# USB_HUB.net
KiCad netlist of a schematic drawn in Altium Designer
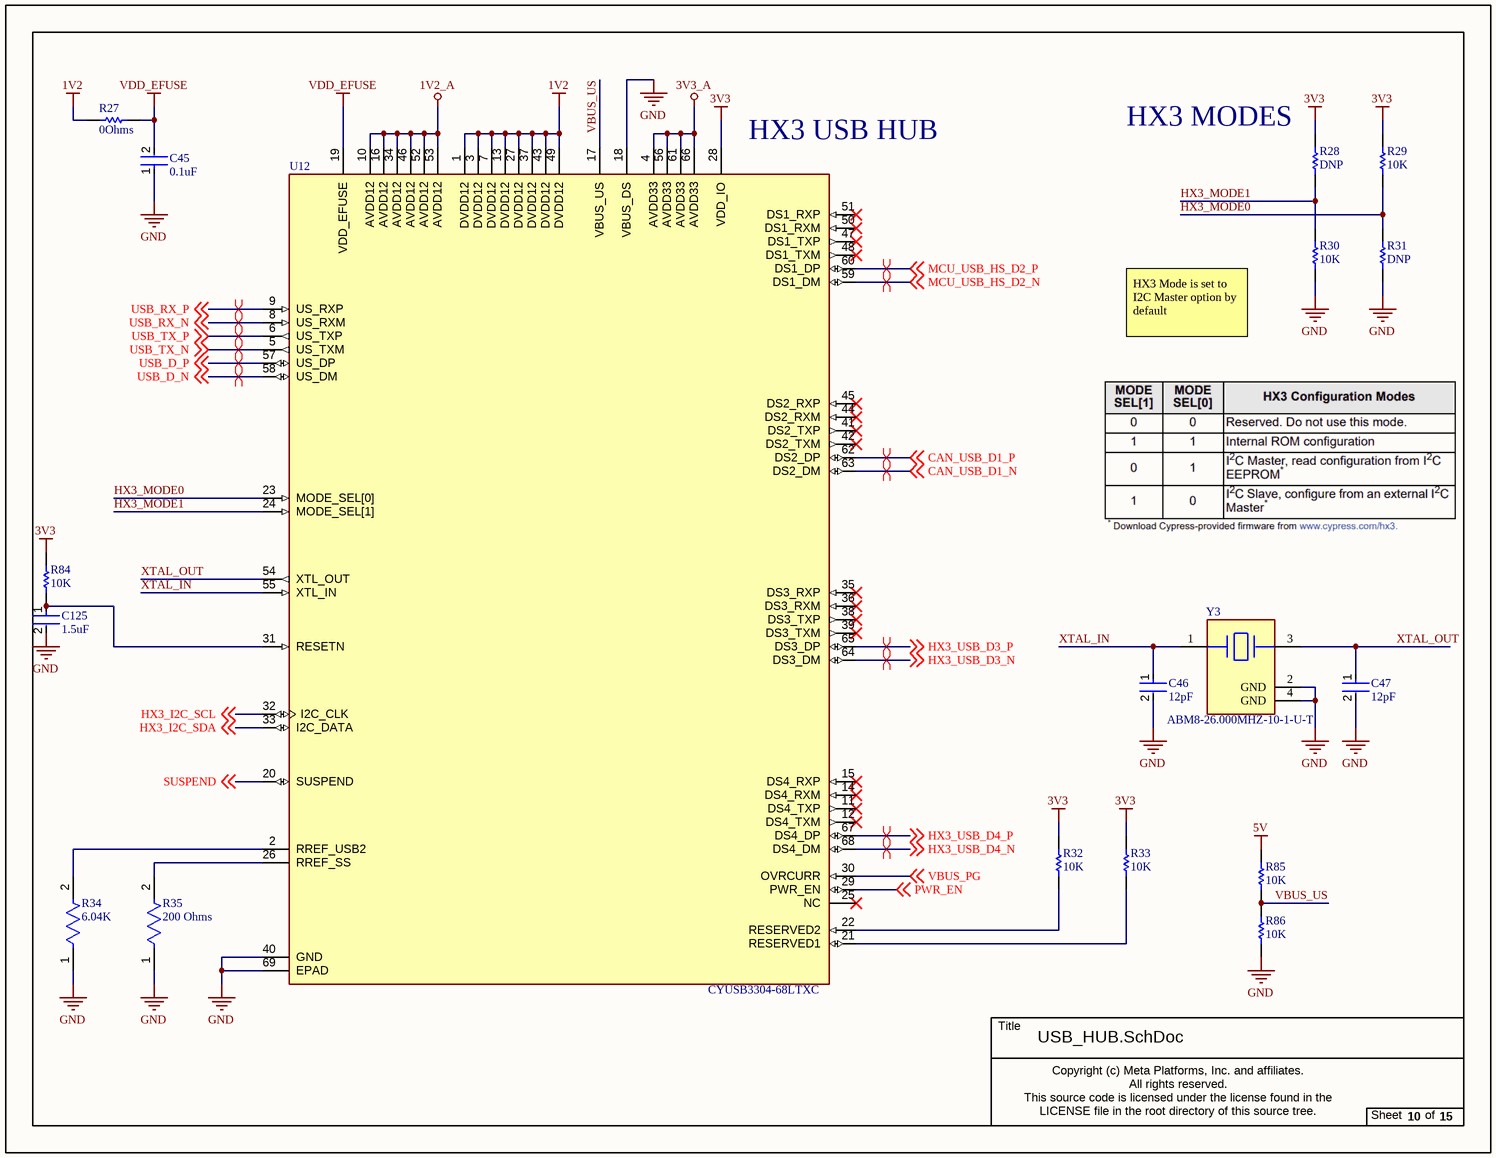
[diagram p0: USB_HUB.SchDoc]

(export (version "E")
  (design (tool "Eeschema 10.0.6"))
  (components
    (comp (ref "C45")
      (value "0.1uF")
      (footprint "FP-CC0201-BA-MFG")
      (description "CAP CER 0.1UF 6.3V X5R 0201")
      (fields (field (name "MANUFACTURER") "Yageo") (field (name "TOLERANCE") "0.1"))
      (libsource (lib "Altium Content Vault") (part "11868f565c42a9108669ba33697ecf6"))
    )
    (comp (ref "C46")
      (value "12pF")
      (footprint "FP-0402-L_1_0_1-W_0_5_0_1-IPC_B")
      (description "General Purpose Ceramic Capacitor, 0402, 12pF, 5%, C0G, 30ppm/°C, 50V")
      (fields (field (name "VOLTAGE") "50V") (field (name "TOLERANCE") "5%"))
      (libsource (lib "Altium Content Vault") (part "b4654b650e69147ec39a6b967a45e02"))
    )
    (comp (ref "C47")
      (value "12pF")
      (footprint "FP-0402-L_1_0_1-W_0_5_0_1-IPC_B")
      (description "General Purpose Ceramic Capacitor, 0402, 12pF, 5%, C0G, 30ppm/°C, 50V")
      (fields (field (name "VOLTAGE") "50V") (field (name "TOLERANCE") "5%"))
      (libsource (lib "Altium Content Vault") (part "b4654b650e69147ec39a6b967a45e02"))
    )
    (comp (ref "C125")
      (value "1.5uF")
      (footprint "FP-C1005-050-0_05-IPC_A")
      (description "Multilayer Ceramic Capacitors 1.5μF ±10% 10V X5R SMD 0402")
      (fields (field (name "TOLERANCE") "10%"))
      (libsource (lib "Altium Content Vault") (part "b4654b650e69147ec39a6b967a45e02"))
    )
    (comp (ref "R27")
      (value "0Ohms")
      (footprint "RESC1005X40X25ML05T10")
      (fields (field (name "PART NUMBER") "CRCW040210K0FKEDHP") (field (name "MANUFACTURER") "Vishay Dale"))
      (libsource (lib "Altium Content Vault") (part "RES"))
    )
    (comp (ref "R28")
      (value "DNP")
      (footprint "RESC1005X40X25ML05T10")
      (fields (field (name "PART NUMBER") "CRCW040210K0FKEDHP") (field (name "MANUFACTURER") "Vishay Dale"))
      (libsource (lib "Altium Content Vault") (part "RES"))
    )
    (comp (ref "R29")
      (value "10K")
      (footprint "RESC1005X40X25ML05T10")
      (fields (field (name "PART NUMBER") "CRCW040210K0FKEDHP") (field (name "MANUFACTURER") "Vishay Dale"))
      (libsource (lib "Altium Content Vault") (part "RES"))
    )
    (comp (ref "R30")
      (value "10K")
      (footprint "RESC1005X40X25ML05T10")
      (fields (field (name "PART NUMBER") "CRCW040210K0FKEDHP") (field (name "MANUFACTURER") "Vishay Dale"))
      (libsource (lib "Altium Content Vault") (part "RES"))
    )
    (comp (ref "R31")
      (value "DNP")
      (footprint "RESC1005X40X25ML05T10")
      (fields (field (name "PART NUMBER") "CRCW040210K0FKEDHP") (field (name "MANUFACTURER") "Vishay Dale"))
      (libsource (lib "Altium Content Vault") (part "RES"))
    )
    (comp (ref "R32")
      (value "10K")
      (footprint "RESC1005X40X25ML05T10")
      (fields (field (name "PART NUMBER") "CRCW040210K0FKEDHP") (field (name "MANUFACTURER") "Vishay Dale"))
      (libsource (lib "Altium Content Vault") (part "RES"))
    )
    (comp (ref "R33")
      (value "10K")
      (footprint "RESC1005X40X25ML05T10")
      (fields (field (name "PART NUMBER") "CRCW040210K0FKEDHP") (field (name "MANUFACTURER") "Vishay Dale"))
      (libsource (lib "Altium Content Vault") (part "RES"))
    )
    (comp (ref "R34")
      (value "6.04K")
      (footprint "FP-RMCF0402-IPC_A")
      (description "6.04kΩ ±1% 0.063W 0402 Thick Film Chip Resistor AEC-Q200 compliant")
      (fields (field (name "TOLERANCE") "1%"))
      (libsource (lib "Altium Content Vault") (part "1029c3af85768c4190bb7ad29bc67b5"))
    )
    (comp (ref "R35")
      (value "200 Ohms")
      (footprint "FP-RMCF0402-IPC_B")
      (description "200Ω ±1% 0.063W 0402 Thick Film Chip Resistor AEC-Q200 compliant")
      (fields (field (name "TOLERANCE") "1%"))
      (libsource (lib "Altium Content Vault") (part "1029c3af85768c4190bb7ad29bc67b5"))
    )
    (comp (ref "R84")
      (value "10K")
      (footprint "RESC1005X40X25ML05T10")
      (fields (field (name "PART NUMBER") "CRCW040210K0FKEDHP") (field (name "MANUFACTURER") "Vishay Dale"))
      (libsource (lib "Altium Content Vault") (part "RES"))
    )
    (comp (ref "R85")
      (value "10K")
      (footprint "RESC1005X40X25ML05T10")
      (fields (field (name "PART NUMBER") "CRCW040210K0FKEDHP") (field (name "MANUFACTURER") "Vishay Dale"))
      (libsource (lib "Altium Content Vault") (part "RES"))
    )
    (comp (ref "R86")
      (value "10K")
      (footprint "RESC1005X40X25ML05T10")
      (fields (field (name "PART NUMBER") "CRCW040210K0FKEDHP") (field (name "MANUFACTURER") "Vishay Dale"))
      (libsource (lib "Altium Content Vault") (part "RES"))
    )
    (comp (ref "U12")
      (value "CYUSB3304-68LTXC")
      (footprint "QFN40P800X800X100-69M")
      (description "IC USB 3.0 HUB 4-PORT 68QFN")
      (fields
        (field (name "MANUFACTURER") "Cypress Semiconductor")
        (field (name "PART NUMBER") "CYUSB3304-68LTXC")
      )
      (libsource (lib "Phalanx") (part "CYUSB3304-68LTXC"))
    )
    (comp (ref "Y3")
      (value "ABM8-26.000MHZ-10-1-U-T")
      (footprint "FP-ABM8-MFG")
      (description "Crystal 26MHz ±10ppm 10pF SMD-4 3.2mm x 2.5mm")
      (fields (field (name "TOLERANCE") "10ppm"))
      (libsource (lib "Altium Content Vault") (part "dfdb7f9a12507849fb681da9a70121c"))
    )
  )
  (nets
    (net (code "1") (name "/HX3_MODE0") (class "Default")
      (node (ref "R29") (pin "1") (pinfunction "1_1") (pintype "passive"))
      (node (ref "R31") (pin "2") (pinfunction "2_2") (pintype "passive"))
      (node (ref "U12") (pin "23") (pinfunction "MODE_SEL[0]_23") (pintype "input"))
    )
    (net (code "2") (name "/HX3_MODE1") (class "Default")
      (node (ref "R28") (pin "1") (pinfunction "1_1") (pintype "passive"))
      (node (ref "R30") (pin "2") (pinfunction "2_2") (pintype "passive"))
      (node (ref "U12") (pin "24") (pinfunction "MODE_SEL[1]_24") (pintype "input"))
    )
    (net (code "3") (name "/VBUS_US") (class "Default")
      (node (ref "R85") (pin "1") (pinfunction "1_1") (pintype "passive"))
      (node (ref "R86") (pin "2") (pinfunction "2_2") (pintype "passive"))
      (node (ref "U12") (pin "17") (pinfunction "VBUS_US_17") (pintype "power_in"))
    )
    (net (code "4") (name "/XTAL_IN") (class "Default")
      (node (ref "C46") (pin "1") (pinfunction "1_1") (pintype "passive"))
      (node (ref "U12") (pin "55") (pinfunction "XTL_IN_55") (pintype "input"))
      (node (ref "Y3") (pin "1") (pinfunction "1_1") (pintype "passive"))
    )
    (net (code "5") (name "/XTAL_OUT") (class "Default")
      (node (ref "C47") (pin "1") (pinfunction "1_1") (pintype "passive"))
      (node (ref "U12") (pin "54") (pinfunction "XTL_OUT_54") (pintype "output"))
      (node (ref "Y3") (pin "3") (pinfunction "3_3") (pintype "passive"))
    )
    (net (code "6") (name "1V2") (class "Default")
      (node (ref "R27") (pin "2") (pinfunction "2_2") (pintype "passive"))
      (node (ref "U12") (pin "1") (pinfunction "DVDD12_1") (pintype "power_in"))
      (node (ref "U12") (pin "13") (pinfunction "DVDD12_13") (pintype "power_in"))
      (node (ref "U12") (pin "27") (pinfunction "DVDD12_27") (pintype "power_in"))
      (node (ref "U12") (pin "3") (pinfunction "DVDD12_3") (pintype "power_in"))
      (node (ref "U12") (pin "37") (pinfunction "DVDD12_37") (pintype "power_in"))
      (node (ref "U12") (pin "43") (pinfunction "DVDD12_43") (pintype "power_in"))
      (node (ref "U12") (pin "49") (pinfunction "DVDD12_49") (pintype "power_in"))
      (node (ref "U12") (pin "7") (pinfunction "DVDD12_7") (pintype "power_in"))
    )
    (net (code "7") (name "1V2_A") (class "Default")
      (node (ref "U12") (pin "10") (pinfunction "AVDD12_10") (pintype "power_in"))
      (node (ref "U12") (pin "16") (pinfunction "AVDD12_16") (pintype "power_in"))
      (node (ref "U12") (pin "34") (pinfunction "AVDD12_34") (pintype "power_in"))
      (node (ref "U12") (pin "46") (pinfunction "AVDD12_46") (pintype "power_in"))
      (node (ref "U12") (pin "52") (pinfunction "AVDD12_52") (pintype "power_in"))
      (node (ref "U12") (pin "53") (pinfunction "AVDD12_53") (pintype "power_in"))
    )
    (net (code "8") (name "3V3") (class "Default")
      (node (ref "R28") (pin "2") (pinfunction "2_2") (pintype "passive"))
      (node (ref "R29") (pin "2") (pinfunction "2_2") (pintype "passive"))
      (node (ref "R32") (pin "2") (pinfunction "2_2") (pintype "passive"))
      (node (ref "R33") (pin "2") (pinfunction "2_2") (pintype "passive"))
      (node (ref "R84") (pin "2") (pinfunction "2_2") (pintype "passive"))
      (node (ref "U12") (pin "28") (pinfunction "VDD_IO_28") (pintype "power_in"))
    )
    (net (code "9") (name "3V3_A") (class "Default")
      (node (ref "U12") (pin "4") (pinfunction "AVDD33_4") (pintype "power_in"))
      (node (ref "U12") (pin "56") (pinfunction "AVDD33_56") (pintype "power_in"))
      (node (ref "U12") (pin "61") (pinfunction "AVDD33_61") (pintype "power_in"))
      (node (ref "U12") (pin "66") (pinfunction "AVDD33_66") (pintype "power_in"))
    )
    (net (code "10") (name "5V") (class "Default")
      (node (ref "R85") (pin "2") (pinfunction "2_2") (pintype "passive"))
    )
    (net (code "11") (name "CAN_USB_D1_N") (class "Default")
      (node (ref "U12") (pin "63") (pinfunction "DS2_DM_63") (pintype "bidirectional"))
    )
    (net (code "12") (name "CAN_USB_D1_P") (class "Default")
      (node (ref "U12") (pin "62") (pinfunction "DS2_DP_62") (pintype "bidirectional"))
    )
    (net (code "13") (name "GND") (class "Default")
      (node (ref "C125") (pin "2") (pinfunction "2_2") (pintype "passive"))
      (node (ref "C45") (pin "1") (pinfunction "1_1") (pintype "passive"))
      (node (ref "C46") (pin "2") (pinfunction "2_2") (pintype "passive"))
      (node (ref "C47") (pin "2") (pinfunction "2_2") (pintype "passive"))
      (node (ref "R30") (pin "1") (pinfunction "1_1") (pintype "passive"))
      (node (ref "R31") (pin "1") (pinfunction "1_1") (pintype "passive"))
      (node (ref "R34") (pin "1") (pinfunction "1_1") (pintype "passive"))
      (node (ref "R35") (pin "1") (pinfunction "1_1") (pintype "passive"))
      (node (ref "R86") (pin "1") (pinfunction "1_1") (pintype "passive"))
      (node (ref "U12") (pin "18") (pinfunction "VBUS_DS_18") (pintype "power_in"))
      (node (ref "U12") (pin "40") (pinfunction "GND_40") (pintype "power_in"))
      (node (ref "U12") (pin "69") (pinfunction "EPAD_69") (pintype "power_in"))
      (node (ref "Y3") (pin "2") (pinfunction "GND_2") (pintype "power_in"))
      (node (ref "Y3") (pin "4") (pinfunction "GND_4") (pintype "power_in"))
    )
    (net (code "14") (name "HX3_I2C_SCL") (class "Default")
      (node (ref "U12") (pin "32") (pinfunction "I2C_CLK_32") (pintype "bidirectional"))
    )
    (net (code "15") (name "HX3_I2C_SDA") (class "Default")
      (node (ref "U12") (pin "33") (pinfunction "I2C_DATA_33") (pintype "bidirectional"))
    )
    (net (code "16") (name "HX3_USB_D3_N") (class "Default")
      (node (ref "U12") (pin "64") (pinfunction "DS3_DM_64") (pintype "bidirectional"))
    )
    (net (code "17") (name "HX3_USB_D3_P") (class "Default")
      (node (ref "U12") (pin "65") (pinfunction "DS3_DP_65") (pintype "bidirectional"))
    )
    (net (code "18") (name "HX3_USB_D4_N") (class "Default")
      (node (ref "U12") (pin "68") (pinfunction "DS4_DM_68") (pintype "bidirectional"))
    )
    (net (code "19") (name "HX3_USB_D4_P") (class "Default")
      (node (ref "U12") (pin "67") (pinfunction "DS4_DP_67") (pintype "bidirectional"))
    )
    (net (code "20") (name "MCU_USB_HS_D2_N") (class "Default")
      (node (ref "U12") (pin "59") (pinfunction "DS1_DM_59") (pintype "bidirectional"))
    )
    (net (code "21") (name "MCU_USB_HS_D2_P") (class "Default")
      (node (ref "U12") (pin "60") (pinfunction "DS1_DP_60") (pintype "bidirectional"))
    )
    (net (code "22") (name "Net-(U12-RESERVED1)") (class "Default")
      (node (ref "R33") (pin "1") (pinfunction "1_1") (pintype "passive"))
      (node (ref "U12") (pin "21") (pinfunction "RESERVED1_21") (pintype "bidirectional"))
    )
    (net (code "23") (name "Net-(U12-RESERVED2)") (class "Default")
      (node (ref "R32") (pin "1") (pinfunction "1_1") (pintype "passive"))
      (node (ref "U12") (pin "22") (pinfunction "RESERVED2_22") (pintype "input"))
    )
    (net (code "24") (name "Net-(U12-RESETN)") (class "Default")
      (node (ref "C125") (pin "1") (pinfunction "1_1") (pintype "passive"))
      (node (ref "R84") (pin "1") (pinfunction "1_1") (pintype "passive"))
      (node (ref "U12") (pin "31") (pinfunction "RESETN_31") (pintype "input"))
    )
    (net (code "25") (name "Net-(U12-RREF_SS)") (class "Default")
      (node (ref "R35") (pin "2") (pinfunction "2_2") (pintype "passive"))
      (node (ref "U12") (pin "26") (pinfunction "RREF_SS_26") (pintype "passive"))
    )
    (net (code "26") (name "Net-(U12-RREF_USB2)") (class "Default")
      (node (ref "R34") (pin "2") (pinfunction "2_2") (pintype "passive"))
      (node (ref "U12") (pin "2") (pinfunction "RREF_USB2_2") (pintype "passive"))
    )
    (net (code "27") (name "PWR_EN") (class "Default")
      (node (ref "U12") (pin "29") (pinfunction "PWR_EN_29") (pintype "bidirectional"))
    )
    (net (code "28") (name "SUSPEND") (class "Default")
      (node (ref "U12") (pin "20") (pinfunction "SUSPEND_20") (pintype "bidirectional"))
    )
    (net (code "29") (name "USB_D_N") (class "Default")
      (node (ref "U12") (pin "58") (pinfunction "US_DM_58") (pintype "bidirectional"))
    )
    (net (code "30") (name "USB_D_P") (class "Default")
      (node (ref "U12") (pin "57") (pinfunction "US_DP_57") (pintype "bidirectional"))
    )
    (net (code "31") (name "USB_RX_N") (class "Default")
      (node (ref "U12") (pin "8") (pinfunction "US_RXM_8") (pintype "input"))
    )
    (net (code "32") (name "USB_RX_P") (class "Default")
      (node (ref "U12") (pin "9") (pinfunction "US_RXP_9") (pintype "input"))
    )
    (net (code "33") (name "USB_TX_N") (class "Default")
      (node (ref "U12") (pin "5") (pinfunction "US_TXM_5") (pintype "output"))
    )
    (net (code "34") (name "USB_TX_P") (class "Default")
      (node (ref "U12") (pin "6") (pinfunction "US_TXP_6") (pintype "output"))
    )
    (net (code "35") (name "VBUS_PG") (class "Default")
      (node (ref "U12") (pin "30") (pinfunction "OVRCURR_30") (pintype "input"))
    )
    (net (code "36") (name "VDD_EFUSE") (class "Default")
      (node (ref "C45") (pin "2") (pinfunction "2_2") (pintype "passive"))
      (node (ref "R27") (pin "1") (pinfunction "1_1") (pintype "passive"))
      (node (ref "U12") (pin "19") (pinfunction "VDD_EFUSE_19") (pintype "power_in"))
    )
    (net (code "37") (name "unconnected-(U12-DS1_RXM-Pad50)") (class "Default")
      (node (ref "U12") (pin "50") (pinfunction "DS1_RXM_50") (pintype "input+no_connect"))
    )
    (net (code "38") (name "unconnected-(U12-DS1_RXP-Pad51)") (class "Default")
      (node (ref "U12") (pin "51") (pinfunction "DS1_RXP_51") (pintype "input+no_connect"))
    )
    (net (code "39") (name "unconnected-(U12-DS1_TXM-Pad48)") (class "Default")
      (node (ref "U12") (pin "48") (pinfunction "DS1_TXM_48") (pintype "output+no_connect"))
    )
    (net (code "40") (name "unconnected-(U12-DS1_TXP-Pad47)") (class "Default")
      (node (ref "U12") (pin "47") (pinfunction "DS1_TXP_47") (pintype "output+no_connect"))
    )
    (net (code "41") (name "unconnected-(U12-DS2_RXM-Pad44)") (class "Default")
      (node (ref "U12") (pin "44") (pinfunction "DS2_RXM_44") (pintype "input+no_connect"))
    )
    (net (code "42") (name "unconnected-(U12-DS2_RXP-Pad45)") (class "Default")
      (node (ref "U12") (pin "45") (pinfunction "DS2_RXP_45") (pintype "input+no_connect"))
    )
    (net (code "43") (name "unconnected-(U12-DS2_TXM-Pad42)") (class "Default")
      (node (ref "U12") (pin "42") (pinfunction "DS2_TXM_42") (pintype "output+no_connect"))
    )
    (net (code "44") (name "unconnected-(U12-DS2_TXP-Pad41)") (class "Default")
      (node (ref "U12") (pin "41") (pinfunction "DS2_TXP_41") (pintype "output+no_connect"))
    )
    (net (code "45") (name "unconnected-(U12-DS3_RXM-Pad36)") (class "Default")
      (node (ref "U12") (pin "36") (pinfunction "DS3_RXM_36") (pintype "input+no_connect"))
    )
    (net (code "46") (name "unconnected-(U12-DS3_RXP-Pad35)") (class "Default")
      (node (ref "U12") (pin "35") (pinfunction "DS3_RXP_35") (pintype "input+no_connect"))
    )
    (net (code "47") (name "unconnected-(U12-DS3_TXM-Pad39)") (class "Default")
      (node (ref "U12") (pin "39") (pinfunction "DS3_TXM_39") (pintype "output+no_connect"))
    )
    (net (code "48") (name "unconnected-(U12-DS3_TXP-Pad38)") (class "Default")
      (node (ref "U12") (pin "38") (pinfunction "DS3_TXP_38") (pintype "output+no_connect"))
    )
    (net (code "49") (name "unconnected-(U12-DS4_RXM-Pad14)") (class "Default")
      (node (ref "U12") (pin "14") (pinfunction "DS4_RXM_14") (pintype "input+no_connect"))
    )
    (net (code "50") (name "unconnected-(U12-DS4_RXP-Pad15)") (class "Default")
      (node (ref "U12") (pin "15") (pinfunction "DS4_RXP_15") (pintype "input+no_connect"))
    )
    (net (code "51") (name "unconnected-(U12-DS4_TXM-Pad12)") (class "Default")
      (node (ref "U12") (pin "12") (pinfunction "DS4_TXM_12") (pintype "output+no_connect"))
    )
    (net (code "52") (name "unconnected-(U12-DS4_TXP-Pad11)") (class "Default")
      (node (ref "U12") (pin "11") (pinfunction "DS4_TXP_11") (pintype "output+no_connect"))
    )
    (net (code "53") (name "unconnected-(U12-NC-Pad25)") (class "Default")
      (node (ref "U12") (pin "25") (pinfunction "NC_25") (pintype "passive+no_connect"))
    )
  )
)
